# 01_MCU.net
KiCad netlist of a schematic drawn in Altium Designer
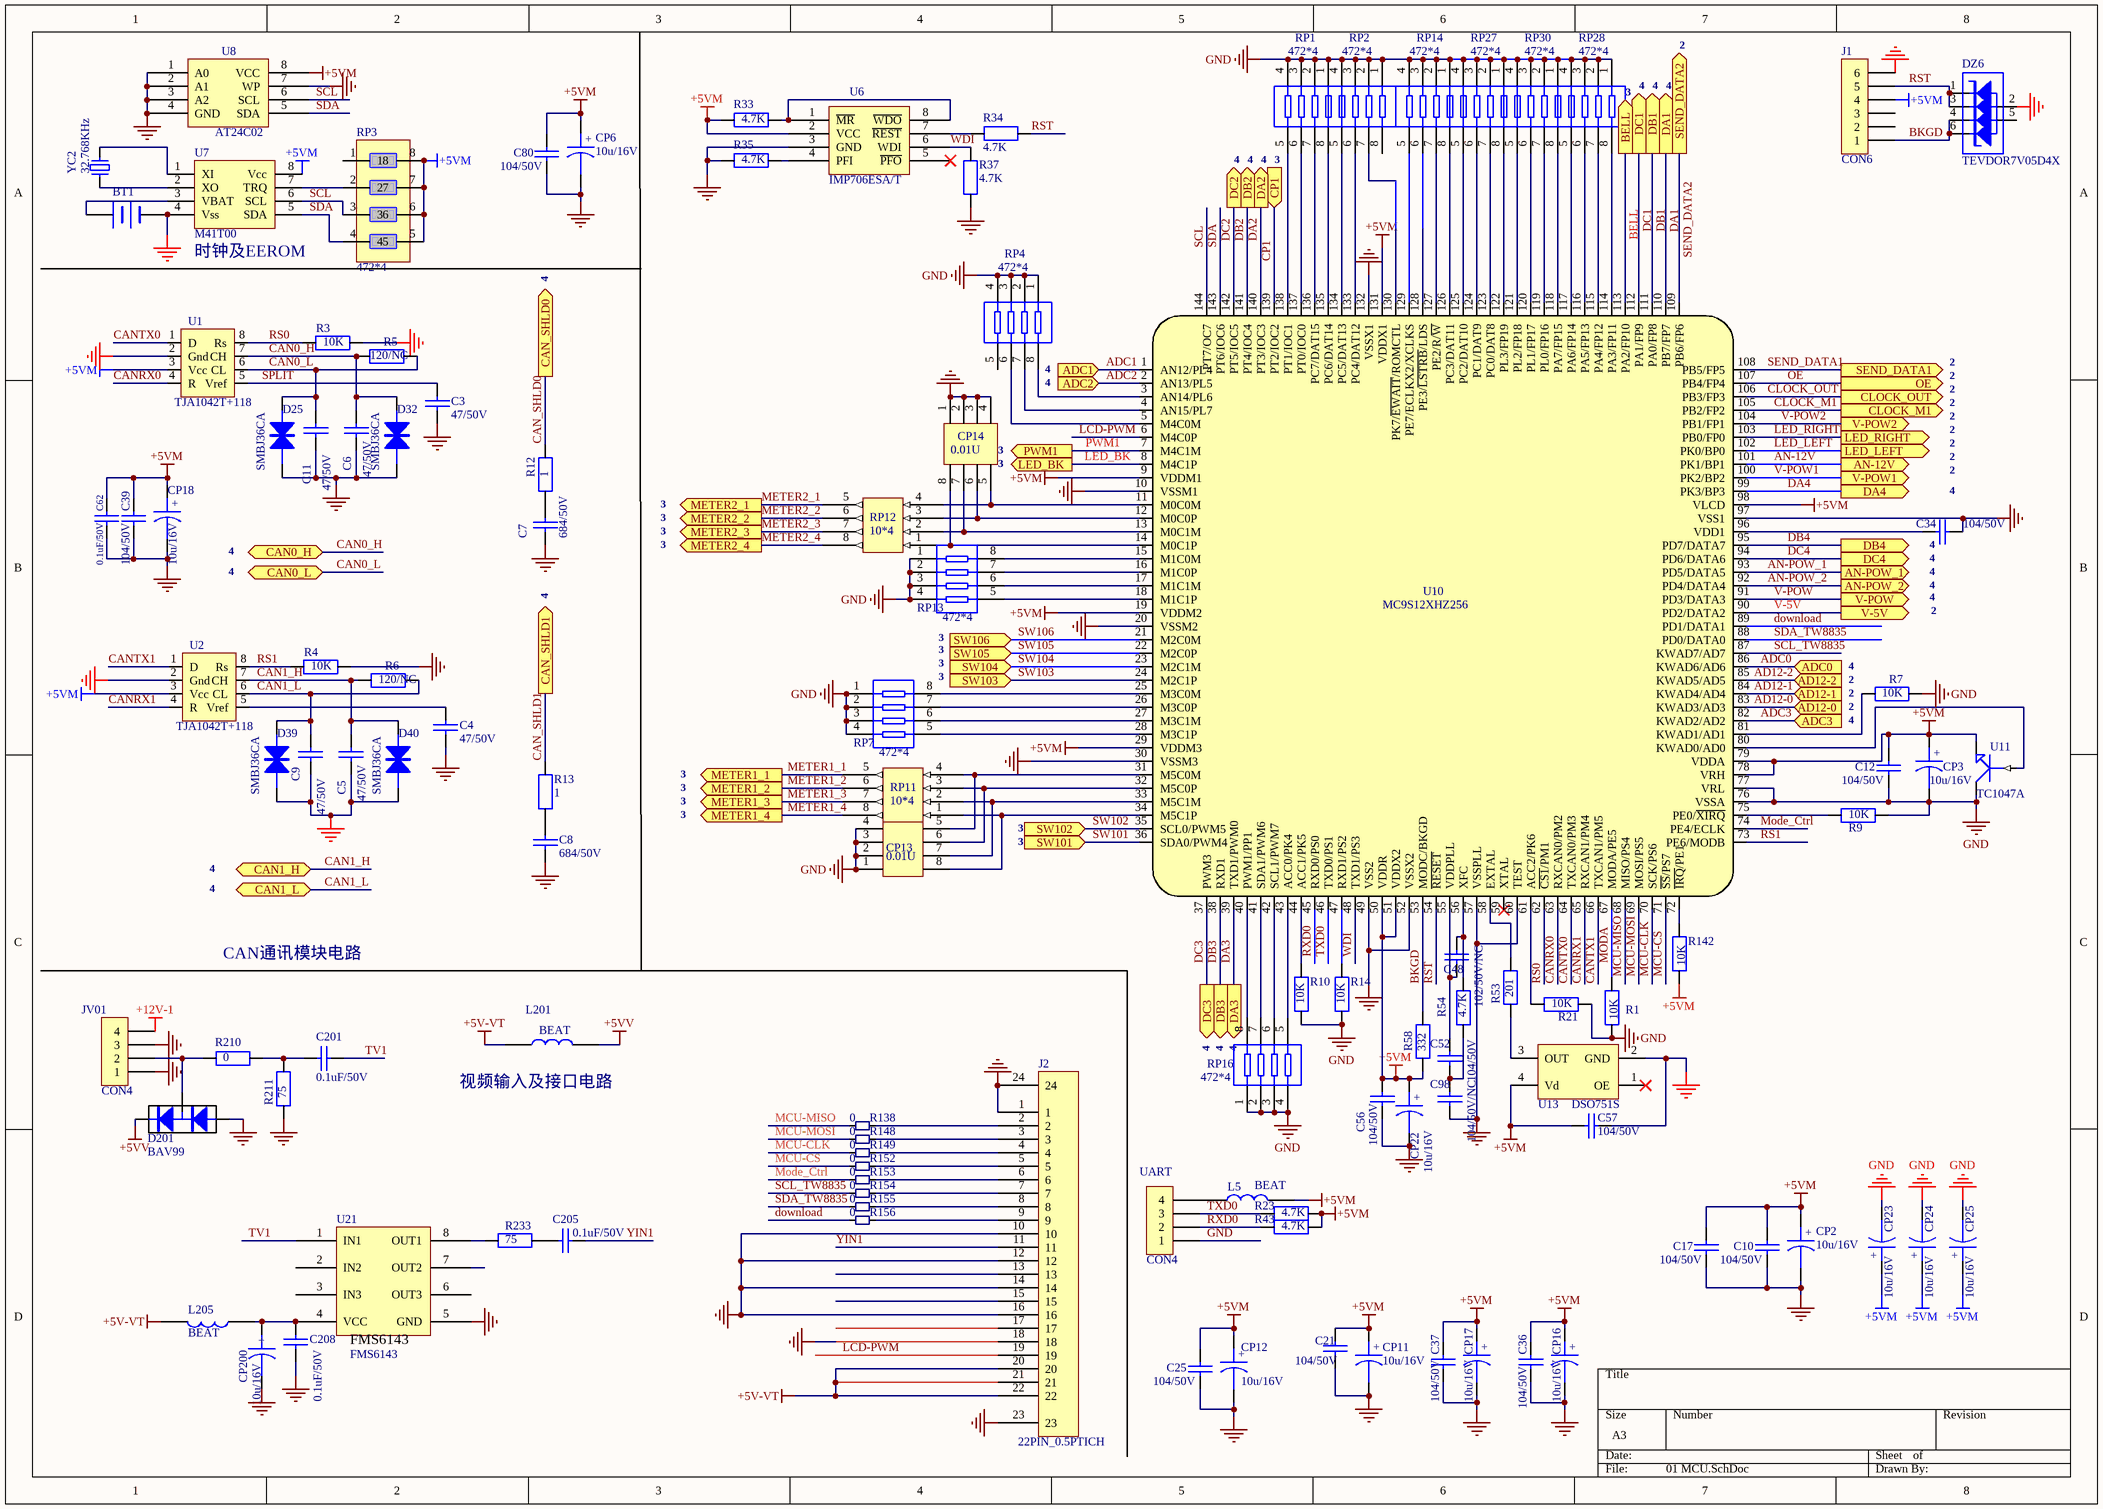
[diagram p0: 01 MCU.SchDoc]

(export (version "E")
  (design (tool "Eeschema 10.0.6"))
  (components
    (comp (ref "BT1")
      (value "~")
      (footprint "Battery 3")
      (description "Battery")
      (libsource (lib "*") (part "BATTERY"))
    )
    (comp (ref "C3")
      (value "47/50V")
      (footprint "CR0805")
      (description "Capacitor")
      (libsource (lib "*") (part "CAP"))
    )
    (comp (ref "C4")
      (value "47/50V")
      (footprint "CR0805")
      (description "Capacitor")
      (libsource (lib "*") (part "CAP"))
    )
    (comp (ref "C5")
      (value "47/50V")
      (footprint "CR0805")
      (description "Capacitor")
      (libsource (lib "*") (part "CAP"))
    )
    (comp (ref "C6")
      (value "47/50V")
      (footprint "CR0805")
      (description "Capacitor")
      (libsource (lib "*") (part "CAP"))
    )
    (comp (ref "C7")
      (value "684/50V")
      (footprint "CR1206")
      (description "Capacitor")
      (libsource (lib "*") (part "CAP"))
    )
    (comp (ref "C8")
      (value "684/50V")
      (footprint "CR1206")
      (description "Capacitor")
      (libsource (lib "*") (part "CAP"))
    )
    (comp (ref "C9")
      (value "47/50V")
      (footprint "CR0805")
      (description "Capacitor")
      (libsource (lib "*") (part "CAP"))
    )
    (comp (ref "C10")
      (value "104/50V")
      (footprint "CR0805")
      (description "Capacitor")
      (libsource (lib "*") (part "CAP"))
    )
    (comp (ref "C11")
      (value "47/50V")
      (footprint "CR0805")
      (description "Capacitor")
      (libsource (lib "*") (part "CAP"))
    )
    (comp (ref "C12")
      (value "104/50V")
      (footprint "CR0805")
      (description "Capacitor")
      (libsource (lib "*") (part "CAP"))
    )
    (comp (ref "C17")
      (value "104/50V")
      (footprint "CR0805")
      (description "Capacitor")
      (libsource (lib "*") (part "CAP"))
    )
    (comp (ref "C21")
      (value "104/50V")
      (footprint "CR0805")
      (description "Capacitor")
      (libsource (lib "*") (part "CAP"))
    )
    (comp (ref "C25")
      (value "104/50V")
      (footprint "CR0805")
      (description "Capacitor")
      (libsource (lib "*") (part "CAP"))
    )
    (comp (ref "C34")
      (value "104/50V")
      (footprint "CR0805")
      (description "Capacitor")
      (libsource (lib "*") (part "CAP"))
    )
    (comp (ref "C36")
      (value "104/50V")
      (footprint "CR0805")
      (description "Capacitor")
      (libsource (lib "*") (part "CAP"))
    )
    (comp (ref "C37")
      (value "104/50V")
      (footprint "CR0805")
      (description "Capacitor")
      (libsource (lib "*") (part "CAP"))
    )
    (comp (ref "C39")
      (value "104/50V")
      (footprint "CR0805")
      (description "Capacitor")
      (libsource (lib "*") (part "CAP"))
    )
    (comp (ref "C48")
      (value "102/50V/NC")
      (footprint "CR0805")
      (description "Capacitor")
      (libsource (lib "*") (part "CAP"))
    )
    (comp (ref "C52")
      (value "104/50V")
      (footprint "CR0805")
      (description "Capacitor")
      (libsource (lib "*") (part "CAP"))
    )
    (comp (ref "C56")
      (value "104/50V")
      (footprint "CR0805")
      (description "Capacitor")
      (libsource (lib "*") (part "CAP"))
    )
    (comp (ref "C57")
      (value "104/50V")
      (footprint "CR0805")
      (description "Capacitor")
      (libsource (lib "*") (part "CAP"))
    )
    (comp (ref "C62")
      (value "0.1uF/50V")
      (footprint "CR0805")
      (description "Capacitor")
      (libsource (lib "*") (part "CAP"))
    )
    (comp (ref "C80")
      (value "104/50V")
      (footprint "CR0805")
      (description "Capacitor")
      (libsource (lib "*") (part "CAP"))
    )
    (comp (ref "C98")
      (value "104/50V/NC")
      (footprint "CR0805")
      (description "Capacitor")
      (libsource (lib "*") (part "CAP"))
    )
    (comp (ref "C201")
      (value "0.1uF/50V")
      (footprint "CR0805")
      (description "贴片电容")
      (libsource (lib "YDM-SQ-1SCH") (part "CAP"))
    )
    (comp (ref "C205")
      (value "0.1uF/50V")
      (footprint "CR0805")
      (description "贴片电容")
      (libsource (lib "YDM-SQ-1SCH") (part "CAP"))
    )
    (comp (ref "C208")
      (value "0.1uF/50V")
      (footprint "CR0805")
      (description "Capacitor")
      (libsource (lib "*") (part "CAP"))
    )
    (comp (ref "CP2")
      (value "10u/16V")
      (footprint "CE1206")
      (description "Capacitor")
      (libsource (lib "*") (part "CAPACITOR POL"))
    )
    (comp (ref "CP3")
      (value "10u/16V")
      (footprint "CE1206")
      (description "Capacitor")
      (libsource (lib "*") (part "CAPACITOR POL"))
    )
    (comp (ref "CP6")
      (value "10u/16V")
      (footprint "CE1206")
      (description "Capacitor")
      (libsource (lib "*") (part "CAPACITOR POL"))
    )
    (comp (ref "CP11")
      (value "10u/16V")
      (footprint "CE1206")
      (description "Capacitor")
      (libsource (lib "*") (part "CAPACITOR POL"))
    )
    (comp (ref "CP12")
      (value "10u/16V")
      (footprint "CE1206")
      (description "Capacitor")
      (libsource (lib "*") (part "CAPACITOR POL"))
    )
    (comp (ref "CP13") (value "0.01U") (footprint "C4") (libsource (lib "*") (part "RC_ARRAY")))
    (comp (ref "CP14") (value "0.01U") (footprint "C4") (libsource (lib "") (part "RC_ARRAY_1")))
    (comp (ref "CP16")
      (value "10u/16V")
      (footprint "CE1206")
      (description "Capacitor")
      (libsource (lib "*") (part "CAPACITOR POL"))
    )
    (comp (ref "CP17")
      (value "10u/16V")
      (footprint "CE1206")
      (description "Capacitor")
      (libsource (lib "*") (part "CAPACITOR POL"))
    )
    (comp (ref "CP18")
      (value "10u/16V")
      (footprint "CE1206")
      (description "Capacitor")
      (libsource (lib "*") (part "CAPACITOR POL"))
    )
    (comp (ref "CP22")
      (value "10u/16V")
      (footprint "CE1206")
      (description "Capacitor")
      (libsource (lib "*") (part "CAPACITOR POL"))
    )
    (comp (ref "CP23")
      (value "10u/16V")
      (footprint "CE1206")
      (description "Capacitor")
      (libsource (lib "*") (part "CAPACITOR POL"))
    )
    (comp (ref "CP24")
      (value "10u/16V")
      (footprint "CE1206")
      (description "Capacitor")
      (libsource (lib "*") (part "CAPACITOR POL"))
    )
    (comp (ref "CP25")
      (value "10u/16V")
      (footprint "CE1206")
      (description "Capacitor")
      (libsource (lib "*") (part "CAPACITOR POL"))
    )
    (comp (ref "CP200")
      (value "10u/16V")
      (footprint "CE1206")
      (description "Capacitor")
      (libsource (lib "") (part "CAPACITOR POL_1"))
    )
    (comp (ref "D25") (value "SMBJ36CA") (footprint "SMB-D") (libsource (lib "YDM-SQ-1SCH") (part "TVS")))
    (comp (ref "D32") (value "SMBJ36CA") (footprint "SMB-D") (libsource (lib "YDM-SQ-1SCH") (part "TVS")))
    (comp (ref "D39") (value "SMBJ36CA") (footprint "SMB-D") (libsource (lib "YDM-SQ-1SCH") (part "TVS")))
    (comp (ref "D40") (value "SMBJ36CA") (footprint "SMB-D") (libsource (lib "YDM-SQ-1SCH") (part "TVS")))
    (comp (ref "D201")
      (value "BAV99")
      (footprint "SOT23")
      (description "双二极管")
      (libsource (lib "YDM-SQ-1SCH") (part "BAV23S"))
    )
    (comp (ref "DZ6")
      (value "TEVDOR7V05D4X")
      (footprint "SOT-457")
      (description "二极管排")
      (libsource (lib "yibiaoschlib") (part "TEVDOR7V05D4X"))
    )
    (comp (ref "J1")
      (value "CON6")
      (footprint "DIP 2X3 2.54mm")
      (description "Connector")
      (libsource (lib "*") (part "CON6"))
    )
    (comp (ref "J2")
      (value "22PIN_0.5PTICH")
      (footprint "FPC-22P")
      (libsource (lib "yibiaoschlib") (part "22PIN_0.5PTICH"))
    )
    (comp (ref "JV01")
      (value "CON4")
      (footprint "DIP 1X4 2.5mm")
      (description "Connector")
      (libsource (lib "YDM-SQ-1SCH") (part "CON4"))
    )
    (comp (ref "L5") (value "BEAT") (footprint "CR0805") (libsource (lib "") (part "BEAT_1")))
    (comp (ref "L201") (value "BEAT") (footprint "CR0805") (libsource (lib "") (part "BEAT_1")))
    (comp (ref "L205") (value "BEAT") (footprint "CR0805") (libsource (lib "YDM-SQ-1SCH") (part "BEAT")))
    (comp (ref "R1")
      (value "10K")
      (footprint "cr0805")
      (description "贴片电阻")
      (libsource (lib "*") (part "RES"))
    )
    (comp (ref "R3")
      (value "10K")
      (footprint "CR0805")
      (description "贴片电阻")
      (libsource (lib "*") (part "RES"))
    )
    (comp (ref "R4")
      (value "10K")
      (footprint "CR0805")
      (description "贴片电阻")
      (libsource (lib "*") (part "RES"))
    )
    (comp (ref "R5")
      (value "120/NC")
      (footprint "CR0805")
      (description "贴片电阻")
      (libsource (lib "*") (part "RES"))
    )
    (comp (ref "R6")
      (value "120/NC")
      (footprint "CR0805")
      (description "贴片电阻")
      (libsource (lib "*") (part "RES"))
    )
    (comp (ref "R7")
      (value "10K")
      (footprint "cr0805")
      (description "贴片电阻")
      (libsource (lib "*") (part "RES"))
    )
    (comp (ref "R9")
      (value "10K")
      (footprint "CR0805")
      (description "贴片电阻")
      (libsource (lib "*") (part "RES"))
    )
    (comp (ref "R10")
      (value "10K")
      (footprint "cr0805")
      (description "贴片电阻")
      (libsource (lib "*") (part "RES"))
    )
    (comp (ref "R12")
      (value "1")
      (footprint "CR0805")
      (description "贴片电阻")
      (libsource (lib "*") (part "RES"))
    )
    (comp (ref "R13")
      (value "1")
      (footprint "CR0805")
      (description "贴片电阻")
      (libsource (lib "*") (part "RES"))
    )
    (comp (ref "R14")
      (value "10K")
      (footprint "cr0805")
      (description "贴片电阻")
      (libsource (lib "*") (part "RES"))
    )
    (comp (ref "R21")
      (value "10K")
      (footprint "cr0805")
      (description "贴片电阻")
      (libsource (lib "*") (part "RES"))
    )
    (comp (ref "R23")
      (value "4.7K")
      (footprint "CR0805")
      (description "贴片电阻")
      (libsource (lib "*") (part "RES"))
    )
    (comp (ref "R33")
      (value "4.7K")
      (footprint "CR0805")
      (description "贴片电阻")
      (libsource (lib "YDM-SQ-1SCH") (part "RES"))
    )
    (comp (ref "R34")
      (value "4.7K")
      (footprint "CR0805")
      (description "贴片电阻")
      (libsource (lib "*") (part "RES"))
    )
    (comp (ref "R35")
      (value "4.7K")
      (footprint "CR0805")
      (description "贴片电阻")
      (libsource (lib "YDM-SQ-1SCH") (part "RES"))
    )
    (comp (ref "R37")
      (value "4.7K")
      (footprint "CR0805")
      (description "贴片电阻")
      (libsource (lib "*") (part "RES"))
    )
    (comp (ref "R43")
      (value "4.7K")
      (footprint "CR0805")
      (description "贴片电阻")
      (libsource (lib "*") (part "RES"))
    )
    (comp (ref "R53")
      (value "201")
      (footprint "CR0805")
      (description "贴片电阻")
      (libsource (lib "*") (part "RES"))
    )
    (comp (ref "R54")
      (value "4.7K")
      (footprint "CR0805")
      (description "贴片电阻")
      (libsource (lib "*") (part "RES"))
    )
    (comp (ref "R58")
      (value "332")
      (footprint "CR0805")
      (description "贴片电阻")
      (libsource (lib "*") (part "RES"))
    )
    (comp (ref "R138")
      (value "0")
      (footprint "CR0805")
      (description "贴片电阻")
      (libsource (lib "YDM-SQ-1SCH") (part "Resister mini"))
    )
    (comp (ref "R142")
      (value "10K")
      (footprint "cr0805")
      (description "贴片电阻")
      (libsource (lib "*") (part "RES"))
    )
    (comp (ref "R148")
      (value "0")
      (footprint "CR0805")
      (description "贴片电阻")
      (libsource (lib "YDM-SQ-1SCH") (part "Resister mini"))
    )
    (comp (ref "R149")
      (value "0")
      (footprint "CR0805")
      (description "贴片电阻")
      (libsource (lib "YDM-SQ-1SCH") (part "Resister mini"))
    )
    (comp (ref "R152")
      (value "0")
      (footprint "CR0805")
      (description "贴片电阻")
      (libsource (lib "YDM-SQ-1SCH") (part "Resister mini"))
    )
    (comp (ref "R153")
      (value "0")
      (footprint "CR0805")
      (description "贴片电阻")
      (libsource (lib "YDM-SQ-1SCH") (part "Resister mini"))
    )
    (comp (ref "R154")
      (value "0")
      (footprint "CR0805")
      (description "贴片电阻")
      (libsource (lib "YDM-SQ-1SCH") (part "Resister mini"))
    )
    (comp (ref "R155")
      (value "0")
      (footprint "CR0805")
      (description "贴片电阻")
      (libsource (lib "YDM-SQ-1SCH") (part "Resister mini"))
    )
    (comp (ref "R156")
      (value "0")
      (footprint "CR0805")
      (description "贴片电阻")
      (libsource (lib "YDM-SQ-1SCH") (part "Resister mini"))
    )
    (comp (ref "R210")
      (value "0")
      (footprint "CR0805")
      (description "贴片电阻")
      (libsource (lib "YDM-SQ-1SCH") (part "RES"))
    )
    (comp (ref "R211")
      (value "75")
      (footprint "CR0805")
      (description "贴片电阻")
      (libsource (lib "YDM-SQ-1SCH") (part "RES"))
    )
    (comp (ref "R233")
      (value "75")
      (footprint "CR0805")
      (description "贴片电阻")
      (libsource (lib "YDM-SQ-1SCH") (part "RES"))
    )
    (comp (ref "RP1")
      (value "472*4")
      (footprint "R4")
      (description "贴片排阻")
      (libsource (lib "*") (part "R_LINE4"))
    )
    (comp (ref "RP2")
      (value "472*4")
      (footprint "R4")
      (description "贴片排阻")
      (libsource (lib "*") (part "R_LINE4"))
    )
    (comp (ref "RP3") (value "472*4") (footprint "R4") (libsource (lib "*") (part "R_ARRAY")))
    (comp (ref "RP4")
      (value "472*4")
      (footprint "R4")
      (description "贴片排阻")
      (libsource (lib "*") (part "R_LINE4"))
    )
    (comp (ref "RP7")
      (value "472*4")
      (footprint "R4")
      (description "贴片排阻")
      (libsource (lib "*") (part "R_LINE4"))
    )
    (comp (ref "RP11") (value "10*4") (footprint "R4") (libsource (lib "*") (part "R_PAI")))
    (comp (ref "RP12") (value "10*4") (footprint "R4") (libsource (lib "*") (part "R_PAI")))
    (comp (ref "RP13")
      (value "472*4")
      (footprint "R4")
      (description "贴片排阻")
      (libsource (lib "*") (part "R_LINE4"))
    )
    (comp (ref "RP14")
      (value "472*4")
      (footprint "R4")
      (description "贴片排阻")
      (libsource (lib "*") (part "R_LINE4"))
    )
    (comp (ref "RP16")
      (value "472*4")
      (footprint "R4")
      (description "贴片排阻")
      (libsource (lib "*") (part "R_LINE4"))
    )
    (comp (ref "RP27")
      (value "472*4")
      (footprint "R4")
      (description "贴片排阻")
      (libsource (lib "*") (part "R_LINE4"))
    )
    (comp (ref "RP28")
      (value "472*4")
      (footprint "R4")
      (description "贴片排阻")
      (libsource (lib "*") (part "R_LINE4"))
    )
    (comp (ref "RP30")
      (value "472*4")
      (footprint "R4")
      (description "贴片排阻")
      (libsource (lib "*") (part "R_LINE4"))
    )
    (comp (ref "U1") (value "TJA1042T+118") (footprint "SO-8") (libsource (lib "*") (part "SN65HVD251")))
    (comp (ref "U2") (value "TJA1042T+118") (footprint "SO-8") (libsource (lib "*") (part "SN65HVD251")))
    (comp (ref "U6") (value "IMP706ESA/T") (footprint "SO-8") (libsource (lib "YDM-SQ-1SCH") (part "IMP706")))
    (comp (ref "U7")
      (value "M41T00")
      (footprint "SO-8")
      (description "IC")
      (libsource (lib "*") (part "M41T00"))
    )
    (comp (ref "U8")
      (value "AT24C02")
      (footprint "SO-8")
      (description "IC")
      (libsource (lib "*") (part "AT24C02"))
    )
    (comp (ref "U10")
      (value "MC9S12XHZ256")
      (footprint "LQFP-144")
      (libsource (lib "YDM-SQ-1SCH") (part "MC9S12XHZ256"))
    )
    (comp (ref "U11") (value "TC1047A") (footprint "SOT23") (libsource (lib "YDM-SQ-1SCH") (part "DTC143")))
    (comp (ref "U13") (value "DSO751S") (footprint "SMD-CYC") (libsource (lib "*") (part "POW_CRY")))
    (comp (ref "U21")
      (value "FMS6143")
      (footprint "SO-8")
      (description "IC-视频滤波")
      (libsource (lib "HNS-SCH") (part "FMS6143"))
    )
    (comp (ref "UART")
      (value "CON4")
      (footprint "DIP 1X4 2.5mm")
      (description "Connector")
      (libsource (lib "YDM-SQ-1SCH") (part "CON4"))
    )
    (comp (ref "YC2")
      (value "32.768KHz")
      (footprint "SM CYC NX3215SA")
      (libsource (lib "*") (part "CRYSTAL0"))
    )
  )
  (nets
    (net (code "1") (name "+5V-VT") (class "Default")
      (node (ref "J2") (pin "20") (pinfunction "20_20") (pintype "passive"))
      (node (ref "J2") (pin "21") (pinfunction "21_21") (pintype "passive"))
      (node (ref "J2") (pin "22") (pinfunction "22_22") (pintype "passive"))
      (node (ref "L201") (pin "1") (pinfunction "1_1") (pintype "passive"))
      (node (ref "L205") (pin "1") (pinfunction "1_1") (pintype "passive"))
    )
    (net (code "2") (name "+5VM") (class "Default")
      (node (ref "C10") (pin "1") (pinfunction "1_1") (pintype "passive"))
      (node (ref "C12") (pin "1") (pinfunction "1_1") (pintype "passive"))
      (node (ref "C17") (pin "1") (pinfunction "1_1") (pintype "passive"))
      (node (ref "C21") (pin "2") (pinfunction "2_2") (pintype "passive"))
      (node (ref "C25") (pin "1") (pinfunction "1_1") (pintype "passive"))
      (node (ref "C36") (pin "1") (pinfunction "1_1") (pintype "passive"))
      (node (ref "C37") (pin "1") (pinfunction "1_1") (pintype "passive"))
      (node (ref "C39") (pin "2") (pinfunction "2_2") (pintype "passive"))
      (node (ref "C56") (pin "1") (pinfunction "1_1") (pintype "passive"))
      (node (ref "C57") (pin "1") (pinfunction "1_1") (pintype "passive"))
      (node (ref "C62") (pin "1") (pinfunction "1_1") (pintype "passive"))
      (node (ref "C80") (pin "1") (pinfunction "1_1") (pintype "passive"))
      (node (ref "CP11") (pin "1") (pinfunction "1_1") (pintype "passive"))
      (node (ref "CP12") (pin "1") (pinfunction "1_1") (pintype "passive"))
      (node (ref "CP16") (pin "1") (pinfunction "1_1") (pintype "passive"))
      (node (ref "CP17") (pin "1") (pinfunction "1_1") (pintype "passive"))
      (node (ref "CP18") (pin "1") (pinfunction "1_1") (pintype "passive"))
      (node (ref "CP2") (pin "1") (pinfunction "1_1") (pintype "passive"))
      (node (ref "CP22") (pin "1") (pinfunction "1_1") (pintype "passive"))
      (node (ref "CP23") (pin "1") (pinfunction "1_1") (pintype "passive"))
      (node (ref "CP24") (pin "1") (pinfunction "1_1") (pintype "passive"))
      (node (ref "CP25") (pin "1") (pinfunction "1_1") (pintype "passive"))
      (node (ref "CP3") (pin "1") (pinfunction "1_1") (pintype "passive"))
      (node (ref "CP6") (pin "1") (pinfunction "1_1") (pintype "passive"))
      (node (ref "J1") (pin "4") (pinfunction "4_4") (pintype "passive"))
      (node (ref "L5") (pin "2") (pinfunction "2_2") (pintype "passive"))
      (node (ref "R142") (pin "2") (pinfunction "2_2") (pintype "passive"))
      (node (ref "R23") (pin "2") (pinfunction "2_2") (pintype "passive"))
      (node (ref "R33") (pin "2") (pinfunction "2_2") (pintype "passive"))
      (node (ref "R43") (pin "2") (pinfunction "2_2") (pintype "passive"))
      (node (ref "R58") (pin "1") (pinfunction "1_1") (pintype "passive"))
      (node (ref "RP3") (pin "5") (pinfunction "5_5") (pintype "passive"))
      (node (ref "RP3") (pin "6") (pinfunction "6_6") (pintype "passive"))
      (node (ref "RP3") (pin "7") (pinfunction "7_7") (pintype "passive"))
      (node (ref "RP3") (pin "8") (pinfunction "8_8") (pintype "passive"))
      (node (ref "U1") (pin "3") (pinfunction "Vcc_3") (pintype "passive"))
      (node (ref "U10") (pin "131") (pinfunction "VDDX1_131") (pintype "passive"))
      (node (ref "U10") (pin "19") (pinfunction "VDDM2_19") (pintype "passive"))
      (node (ref "U10") (pin "29") (pinfunction "VDDM3_29") (pintype "passive"))
      (node (ref "U10") (pin "50") (pinfunction "VDDR_50") (pintype "passive"))
      (node (ref "U10") (pin "51") (pinfunction "VDDX2_51") (pintype "passive"))
      (node (ref "U10") (pin "78") (pinfunction "VRH_78") (pintype "passive"))
      (node (ref "U10") (pin "79") (pinfunction "VDDA_79") (pintype "passive"))
      (node (ref "U10") (pin "9") (pinfunction "VDDM1_9") (pintype "passive"))
      (node (ref "U10") (pin "98") (pinfunction "VLCD_98") (pintype "passive"))
      (node (ref "U11") (pin "1") (pinfunction "E_1") (pintype "passive"))
      (node (ref "U13") (pin "4") (pinfunction "Vd_4") (pintype "passive"))
      (node (ref "U2") (pin "3") (pinfunction "Vcc_3") (pintype "passive"))
      (node (ref "U6") (pin "2") (pinfunction "VCC_2") (pintype "passive"))
      (node (ref "U7") (pin "8") (pinfunction "Vcc_8") (pintype "passive"))
      (node (ref "U8") (pin "8") (pinfunction "VCC_8") (pintype "passive"))
    )
    (net (code "3") (name "+5VV") (class "Default")
      (node (ref "D201") (pin "2") (pintype "passive"))
      (node (ref "L201") (pin "2") (pinfunction "2_2") (pintype "passive"))
    )
    (net (code "4") (name "+12V-1") (class "Default")
      (node (ref "JV01") (pin "4") (pinfunction "4_4") (pintype "passive"))
    )
    (net (code "6") (name "/AD12-0") (class "Default")
      (node (ref "U10") (pin "83") (pinfunction "KWAD3/AD3_83") (pintype "passive"))
    )
    (net (code "7") (name "/AD12-1") (class "Default")
      (node (ref "U10") (pin "84") (pinfunction "KWAD4/AD4_84") (pintype "passive"))
    )
    (net (code "8") (name "/AD12-2") (class "Default")
      (node (ref "U10") (pin "85") (pinfunction "KWAD5/AD5_85") (pintype "passive"))
    )
    (net (code "9") (name "/ADC0") (class "Default")
      (node (ref "U10") (pin "86") (pinfunction "KWAD6/AD6_86") (pintype "passive"))
    )
    (net (code "10") (name "/ADC1") (class "Default")
      (node (ref "U10") (pin "1") (pinfunction "AN12/PL4_1") (pintype "passive"))
    )
    (net (code "11") (name "/ADC2") (class "Default")
      (node (ref "U10") (pin "2") (pinfunction "AN13/PL5_2") (pintype "passive"))
    )
    (net (code "12") (name "/ADC3") (class "Default")
      (node (ref "U10") (pin "82") (pinfunction "KWAD2/AD2_82") (pintype "passive"))
    )
    (net (code "13") (name "/AN-12V") (class "Default")
      (node (ref "U10") (pin "101") (pinfunction "PK1/BP1_101") (pintype "passive"))
    )
    (net (code "14") (name "/AN-POW_1") (class "Default")
      (node (ref "U10") (pin "93") (pinfunction "PD5/DATA5_93") (pintype "passive"))
    )
    (net (code "15") (name "/AN-POW_2") (class "Default")
      (node (ref "U10") (pin "92") (pinfunction "PD4/DATA4_92") (pintype "passive"))
    )
    (net (code "16") (name "/BELL") (class "Default")
      (node (ref "U10") (pin "113") (pinfunction "PA2/FP10_113") (pintype "passive"))
    )
    (net (code "17") (name "/BKGD") (class "Default")
      (node (ref "DZ6") (pin "4") (pintype "passive"))
      (node (ref "DZ6") (pin "6") (pintype "passive"))
      (node (ref "J1") (pin "1") (pinfunction "1_1") (pintype "passive"))
      (node (ref "R58") (pin "2") (pinfunction "2_2") (pintype "passive"))
      (node (ref "U10") (pin "53") (pinfunction "MODC/BKGD_53") (pintype "passive"))
    )
    (net (code "18") (name "/CAN0_H") (class "Default")
      (node (ref "C6") (pin "2") (pinfunction "2_2") (pintype "passive"))
      (node (ref "D32") (pin "2") (pinfunction "2_2") (pintype "passive"))
      (node (ref "R5") (pin "2") (pinfunction "2_2") (pintype "passive"))
      (node (ref "U1") (pin "7") (pinfunction "CH_7") (pintype "passive"))
    )
    (net (code "19") (name "/CAN0_L") (class "Default")
      (node (ref "C11") (pin "2") (pinfunction "2_2") (pintype "passive"))
      (node (ref "D25") (pin "2") (pinfunction "2_2") (pintype "passive"))
      (node (ref "R5") (pin "1") (pinfunction "1_1") (pintype "passive"))
      (node (ref "U1") (pin "6") (pinfunction "CL_6") (pintype "passive"))
    )
    (net (code "20") (name "/CAN1_H") (class "Default")
      (node (ref "C5") (pin "2") (pinfunction "2_2") (pintype "passive"))
      (node (ref "D40") (pin "2") (pinfunction "2_2") (pintype "passive"))
      (node (ref "R6") (pin "2") (pinfunction "2_2") (pintype "passive"))
      (node (ref "U2") (pin "7") (pinfunction "CH_7") (pintype "passive"))
    )
    (net (code "21") (name "/CAN1_L") (class "Default")
      (node (ref "C9") (pin "2") (pinfunction "2_2") (pintype "passive"))
      (node (ref "D39") (pin "2") (pinfunction "2_2") (pintype "passive"))
      (node (ref "R6") (pin "1") (pinfunction "1_1") (pintype "passive"))
      (node (ref "U2") (pin "6") (pinfunction "CL_6") (pintype "passive"))
    )
    (net (code "22") (name "/CANRX0") (class "Default")
      (node (ref "U1") (pin "4") (pinfunction "R_4") (pintype "passive"))
      (node (ref "U10") (pin "63") (pinfunction "RXCAN0/PM2_63") (pintype "passive"))
    )
    (net (code "23") (name "/CANRX1") (class "Default")
      (node (ref "U10") (pin "65") (pinfunction "RXCAN1/PM4_65") (pintype "passive"))
      (node (ref "U2") (pin "4") (pinfunction "R_4") (pintype "passive"))
    )
    (net (code "24") (name "/CANTX0") (class "Default")
      (node (ref "U1") (pin "1") (pinfunction "D_1") (pintype "passive"))
      (node (ref "U10") (pin "64") (pinfunction "TXCAN0/PM3_64") (pintype "passive"))
    )
    (net (code "25") (name "/CANTX1") (class "Default")
      (node (ref "U10") (pin "66") (pinfunction "TXCAN1/PM5_66") (pintype "passive"))
      (node (ref "U2") (pin "1") (pinfunction "D_1") (pintype "passive"))
    )
    (net (code "26") (name "/CAN_SHLD0") (class "Default")
      (node (ref "R12") (pin "2") (pinfunction "2_2") (pintype "passive"))
    )
    (net (code "27") (name "/CAN_SHLD1") (class "Default")
      (node (ref "R13") (pin "2") (pinfunction "2_2") (pintype "passive"))
    )
    (net (code "28") (name "/CLOCK_M1") (class "Default")
      (node (ref "U10") (pin "105") (pinfunction "PB2/FP2_105") (pintype "passive"))
    )
    (net (code "29") (name "/CLOCK_OUT") (class "Default")
      (node (ref "U10") (pin "106") (pinfunction "PB3/FP3_106") (pintype "passive"))
    )
    (net (code "30") (name "/CP1") (class "Default")
      (node (ref "U10") (pin "139") (pinfunction "PT2/IOC2_139") (pintype "passive"))
    )
    (net (code "31") (name "/DA1") (class "Default")
      (node (ref "U10") (pin "110") (pinfunction "PB7/FP7_110") (pintype "passive"))
    )
    (net (code "32") (name "/DA2") (class "Default")
      (node (ref "U10") (pin "140") (pinfunction "PT3/IOC3_140") (pintype "passive"))
    )
    (net (code "33") (name "/DA3") (class "Default")
      (node (ref "U10") (pin "39") (pinfunction "TXD1/PWM0_39") (pintype "passive"))
    )
    (net (code "34") (name "/DA4") (class "Default")
      (node (ref "U10") (pin "99") (pinfunction "PK3/BP3_99") (pintype "passive"))
    )
    (net (code "35") (name "/DB1") (class "Default")
      (node (ref "U10") (pin "111") (pinfunction "PA0/FP8_111") (pintype "passive"))
    )
    (net (code "36") (name "/DB2") (class "Default")
      (node (ref "U10") (pin "141") (pinfunction "PT4/IOC4_141") (pintype "passive"))
    )
    (net (code "37") (name "/DB3") (class "Default")
      (node (ref "U10") (pin "38") (pinfunction "RXD1_38") (pintype "passive"))
    )
    (net (code "38") (name "/DB4") (class "Default")
      (node (ref "U10") (pin "95") (pinfunction "PD7/DATA7_95") (pintype "passive"))
    )
    (net (code "39") (name "/DC1") (class "Default")
      (node (ref "U10") (pin "112") (pinfunction "PA1/FP9_112") (pintype "passive"))
    )
    (net (code "40") (name "/DC2") (class "Default")
      (node (ref "U10") (pin "142") (pinfunction "PT5/IOC5_142") (pintype "passive"))
    )
    (net (code "41") (name "/DC3") (class "Default")
      (node (ref "U10") (pin "37") (pinfunction "PWM3_37") (pintype "passive"))
    )
    (net (code "42") (name "/DC4") (class "Default")
      (node (ref "U10") (pin "94") (pinfunction "PD6/DATA6_94") (pintype "passive"))
    )
    (net (code "43") (name "/LCD-PWM") (class "Default")
      (node (ref "J2") (pin "19") (pinfunction "19_19") (pintype "passive"))
      (node (ref "U10") (pin "6") (pinfunction "M4C0P_6") (pintype "passive"))
    )
    (net (code "44") (name "/LED_BK") (class "Default")
      (node (ref "U10") (pin "8") (pinfunction "M4C1P_8") (pintype "passive"))
    )
    (net (code "45") (name "/LED_LEFT") (class "Default")
      (node (ref "U10") (pin "102") (pinfunction "PK0/BP0_102") (pintype "passive"))
    )
    (net (code "46") (name "/LED_RIGHT") (class "Default")
      (node (ref "U10") (pin "103") (pinfunction "PB0/FP0_103") (pintype "passive"))
    )
    (net (code "47") (name "/MCU-CLK") (class "Default")
      (node (ref "R149") (pin "2") (pinfunction "2_2") (pintype "passive"))
      (node (ref "U10") (pin "70") (pinfunction "SCK/PS6_70") (pintype "passive"))
    )
    (net (code "48") (name "/MCU-CS") (class "Default")
      (node (ref "R152") (pin "2") (pinfunction "2_2") (pintype "passive"))
      (node (ref "U10") (pin "71") (pinfunction "~{SS}/PS7_71") (pintype "passive"))
    )
    (net (code "49") (name "/MCU-MISO") (class "Default")
      (node (ref "R138") (pin "2") (pinfunction "2_2") (pintype "passive"))
      (node (ref "U10") (pin "68") (pinfunction "MISO/PS4_68") (pintype "passive"))
    )
    (net (code "50") (name "/MCU-MOSI") (class "Default")
      (node (ref "R148") (pin "2") (pinfunction "2_2") (pintype "passive"))
      (node (ref "U10") (pin "69") (pinfunction "MOSI/PS5_69") (pintype "passive"))
    )
    (net (code "51") (name "/METER1_1") (class "Default")
      (node (ref "RP11") (pin "5") (pinfunction "5_5") (pintype "output"))
    )
    (net (code "52") (name "/METER1_2") (class "Default")
      (node (ref "RP11") (pin "6") (pinfunction "6_6") (pintype "output"))
    )
    (net (code "53") (name "/METER1_3") (class "Default")
      (node (ref "RP11") (pin "7") (pinfunction "7_7") (pintype "output"))
    )
    (net (code "54") (name "/METER1_4") (class "Default")
      (node (ref "RP11") (pin "8") (pinfunction "8_8") (pintype "output"))
    )
    (net (code "55") (name "/METER2_1") (class "Default")
      (node (ref "RP12") (pin "5") (pinfunction "5_5") (pintype "output"))
    )
    (net (code "56") (name "/METER2_2") (class "Default")
      (node (ref "RP12") (pin "6") (pinfunction "6_6") (pintype "output"))
    )
    (net (code "57") (name "/METER2_3") (class "Default")
      (node (ref "RP12") (pin "7") (pinfunction "7_7") (pintype "output"))
    )
    (net (code "58") (name "/METER2_4") (class "Default")
      (node (ref "RP12") (pin "8") (pinfunction "8_8") (pintype "output"))
    )
    (net (code "59") (name "/MODA") (class "Default")
      (node (ref "R1") (pin "1") (pinfunction "1_1") (pintype "passive"))
      (node (ref "U10") (pin "67") (pinfunction "MODA/PE5_67") (pintype "passive"))
    )
    (net (code "60") (name "/Mode_Ctrl") (class "Default")
      (node (ref "R153") (pin "2") (pinfunction "2_2") (pintype "passive"))
      (node (ref "U10") (pin "74") (pinfunction "PE4/ECLK_74") (pintype "passive"))
    )
    (net (code "61") (name "/OE") (class "Default")
      (node (ref "U10") (pin "107") (pinfunction "PB4/FP4_107") (pintype "passive"))
    )
    (net (code "62") (name "/PWM1") (class "Default")
      (node (ref "U10") (pin "7") (pinfunction "M4C1M_7") (pintype "passive"))
    )
    (net (code "63") (name "/RS0") (class "Default")
      (node (ref "R3") (pin "1") (pinfunction "1_1") (pintype "passive"))
      (node (ref "U1") (pin "8") (pinfunction "Rs_8") (pintype "passive"))
      (node (ref "U10") (pin "62") (pinfunction "~{CS1}/PM1_62") (pintype "passive"))
    )
    (net (code "64") (name "/RS1") (class "Default")
      (node (ref "R4") (pin "1") (pinfunction "1_1") (pintype "passive"))
      (node (ref "U10") (pin "73") (pinfunction "PE6/MODB_73") (pintype "passive"))
      (node (ref "U2") (pin "8") (pinfunction "Rs_8") (pintype "passive"))
    )
    (net (code "65") (name "/RST") (class "Default")
      (node (ref "DZ6") (pin "1") (pintype "passive"))
      (node (ref "DZ6") (pin "3") (pintype "passive"))
      (node (ref "J1") (pin "5") (pinfunction "5_5") (pintype "passive"))
      (node (ref "R34") (pin "2") (pinfunction "2_2") (pintype "passive"))
      (node (ref "U10") (pin "54") (pinfunction "~{RESET}_54") (pintype "passive"))
    )
    (net (code "66") (name "/RXD0") (class "Default")
      (node (ref "R43") (pin "1") (pinfunction "1_1") (pintype "passive"))
      (node (ref "U10") (pin "45") (pinfunction "RXD0/PS0_45") (pintype "passive"))
      (node (ref "UART") (pin "2") (pinfunction "2_2") (pintype "passive"))
    )
    (net (code "67") (name "/SCL") (class "Default")
      (node (ref "RP3") (pin "3") (pinfunction "3_3") (pintype "passive"))
      (node (ref "U10") (pin "144") (pinfunction "PT7/OC7_144") (pintype "passive"))
      (node (ref "U7") (pin "6") (pinfunction "SCL_6") (pintype "passive"))
      (node (ref "U8") (pin "6") (pinfunction "SCL_6") (pintype "passive"))
    )
    (net (code "68") (name "/SCL_TW8835") (class "Default")
      (node (ref "R154") (pin "2") (pinfunction "2_2") (pintype "passive"))
      (node (ref "U10") (pin "87") (pinfunction "KWAD7/AD7_87") (pintype "passive"))
    )
    (net (code "69") (name "/SDA") (class "Default")
      (node (ref "RP3") (pin "4") (pinfunction "4_4") (pintype "passive"))
      (node (ref "U10") (pin "143") (pinfunction "PT6/IOC6_143") (pintype "passive"))
      (node (ref "U7") (pin "5") (pinfunction "SDA_5") (pintype "passive"))
      (node (ref "U8") (pin "5") (pinfunction "SDA_5") (pintype "passive"))
    )
    (net (code "70") (name "/SDA_TW8835") (class "Default")
      (node (ref "R155") (pin "2") (pinfunction "2_2") (pintype "passive"))
      (node (ref "U10") (pin "88") (pinfunction "PD0/DATA0_88") (pintype "passive"))
    )
    (net (code "71") (name "/SEND_DATA1") (class "Default")
      (node (ref "U10") (pin "108") (pinfunction "PB5/FP5_108") (pintype "passive"))
    )
    (net (code "72") (name "/SEND_DATA2") (class "Default")
      (node (ref "U10") (pin "109") (pinfunction "PB6/FP6_109") (pintype "passive"))
    )
    (net (code "73") (name "/SPLIT") (class "Default")
      (node (ref "C3") (pin "1") (pinfunction "1_1") (pintype "passive"))
      (node (ref "U1") (pin "5") (pinfunction "Vref_5") (pintype "passive"))
    )
    (net (code "74") (name "/SW101") (class "Default")
      (node (ref "U10") (pin "36") (pinfunction "SDA0/PWM4_36") (pintype "passive"))
    )
    (net (code "75") (name "/SW102") (class "Default")
      (node (ref "U10") (pin "35") (pinfunction "SCL0/PWM5_35") (pintype "passive"))
    )
    (net (code "76") (name "/SW103") (class "Default")
      (node (ref "U10") (pin "24") (pinfunction "M2C1P_24") (pintype "passive"))
    )
    (net (code "77") (name "/SW104") (class "Default")
      (node (ref "U10") (pin "23") (pinfunction "M2C1M_23") (pintype "passive"))
    )
    (net (code "78") (name "/SW105") (class "Default")
      (node (ref "U10") (pin "22") (pinfunction "M2C0P_22") (pintype "passive"))
    )
    (net (code "79") (name "/SW106") (class "Default")
      (node (ref "U10") (pin "21") (pinfunction "M2C0M_21") (pintype "passive"))
    )
    (net (code "80") (name "/TV1") (class "Default")
      (node (ref "C201") (pin "2") (pinfunction "2_2") (pintype "passive"))
      (node (ref "U21") (pin "1") (pinfunction "IN1_1") (pintype "passive"))
    )
    (net (code "81") (name "/TXD0") (class "Default")
      (node (ref "R23") (pin "1") (pinfunction "1_1") (pintype "passive"))
      (node (ref "U10") (pin "46") (pinfunction "TXD0/PS1_46") (pintype "passive"))
      (node (ref "UART") (pin "3") (pinfunction "3_3") (pintype "passive"))
    )
    (net (code "82") (name "/V-5V") (class "Default")
      (node (ref "U10") (pin "90") (pinfunction "PD2/DATA2_90") (pintype "passive"))
    )
    (net (code "83") (name "/V-POW") (class "Default")
      (node (ref "U10") (pin "91") (pinfunction "PD3/DATA3_91") (pintype "passive"))
    )
    (net (code "84") (name "/V-POW1") (class "Default")
      (node (ref "U10") (pin "100") (pinfunction "PK2/BP2_100") (pintype "passive"))
    )
    (net (code "85") (name "/V-POW2") (class "Default")
      (node (ref "U10") (pin "104") (pinfunction "PB1/FP1_104") (pintype "passive"))
    )
    (net (code "86") (name "/WDI") (class "Default")
      (node (ref "R37") (pin "1") (pinfunction "1_1") (pintype "passive"))
      (node (ref "U10") (pin "48") (pinfunction "TXD1/PS3_48") (pintype "passive"))
      (node (ref "U6") (pin "6") (pinfunction "WDI_6") (pintype "passive"))
    )
    (net (code "87") (name "/YIN1") (class "Default")
      (node (ref "C205") (pin "2") (pinfunction "2_2") (pintype "passive"))
      (node (ref "J2") (pin "11") (pinfunction "11_11") (pintype "passive"))
    )
    (net (code "88") (name "/download") (class "Default")
      (node (ref "R156") (pin "2") (pinfunction "2_2") (pintype "passive"))
      (node (ref "U10") (pin "89") (pinfunction "PD1/DATA1_89") (pintype "passive"))
    )
    (net (code "89") (name "GND") (class "Default")
      (node (ref "BT1") (pin "2") (pinfunction "-_2") (pintype "passive"))
      (node (ref "C10") (pin "2") (pinfunction "2_2") (pintype "passive"))
      (node (ref "C11") (pin "1") (pinfunction "1_1") (pintype "passive"))
      (node (ref "C12") (pin "2") (pinfunction "2_2") (pintype "passive"))
      (node (ref "C17") (pin "2") (pinfunction "2_2") (pintype "passive"))
      (node (ref "C208") (pin "2") (pinfunction "2_2") (pintype "passive"))
      (node (ref "C21") (pin "1") (pinfunction "1_1") (pintype "passive"))
      (node (ref "C25") (pin "2") (pinfunction "2_2") (pintype "passive"))
      (node (ref "C3") (pin "2") (pinfunction "2_2") (pintype "passive"))
      (node (ref "C34") (pin "2") (pinfunction "2_2") (pintype "passive"))
      (node (ref "C36") (pin "2") (pinfunction "2_2") (pintype "passive"))
      (node (ref "C37") (pin "2") (pinfunction "2_2") (pintype "passive"))
      (node (ref "C39") (pin "1") (pinfunction "1_1") (pintype "passive"))
      (node (ref "C4") (pin "2") (pinfunction "2_2") (pintype "passive"))
      (node (ref "C5") (pin "1") (pinfunction "1_1") (pintype "passive"))
      (node (ref "C56") (pin "2") (pinfunction "2_2") (pintype "passive"))
      (node (ref "C57") (pin "2") (pinfunction "2_2") (pintype "passive"))
      (node (ref "C6") (pin "1") (pinfunction "1_1") (pintype "passive"))
      (node (ref "C62") (pin "2") (pinfunction "2_2") (pintype "passive"))
      (node (ref "C7") (pin "2") (pinfunction "2_2") (pintype "passive"))
      (node (ref "C8") (pin "2") (pinfunction "2_2") (pintype "passive"))
      (node (ref "C80") (pin "2") (pinfunction "2_2") (pintype "passive"))
      (node (ref "C9") (pin "1") (pinfunction "1_1") (pintype "passive"))
      (node (ref "C98") (pin "2") (pinfunction "2_2") (pintype "passive"))
      (node (ref "CP11") (pin "2") (pinfunction "2_2") (pintype "passive"))
      (node (ref "CP12") (pin "2") (pinfunction "2_2") (pintype "passive"))
      (node (ref "CP13") (pin "1") (pinfunction "1_1") (pintype "passive"))
      (node (ref "CP13") (pin "2") (pinfunction "2_2") (pintype "passive"))
      (node (ref "CP13") (pin "3") (pinfunction "3_3") (pintype "passive"))
      (node (ref "CP13") (pin "4") (pinfunction "4_4") (pintype "passive"))
      (node (ref "CP14") (pin "1") (pinfunction "1_1") (pintype "passive"))
      (node (ref "CP14") (pin "2") (pinfunction "2_2") (pintype "passive"))
      (node (ref "CP14") (pin "3") (pinfunction "3_3") (pintype "passive"))
      (node (ref "CP14") (pin "4") (pinfunction "4_4") (pintype "passive"))
      (node (ref "CP16") (pin "2") (pinfunction "2_2") (pintype "passive"))
      (node (ref "CP17") (pin "2") (pinfunction "2_2") (pintype "passive"))
      (node (ref "CP18") (pin "2") (pinfunction "2_2") (pintype "passive"))
      (node (ref "CP2") (pin "2") (pinfunction "2_2") (pintype "passive"))
      (node (ref "CP200") (pin "2") (pinfunction "2_2") (pintype "passive"))
      (node (ref "CP22") (pin "2") (pinfunction "2_2") (pintype "passive"))
      (node (ref "CP23") (pin "2") (pinfunction "2_2") (pintype "passive"))
      (node (ref "CP24") (pin "2") (pinfunction "2_2") (pintype "passive"))
      (node (ref "CP25") (pin "2") (pinfunction "2_2") (pintype "passive"))
      (node (ref "CP3") (pin "2") (pinfunction "2_2") (pintype "passive"))
      (node (ref "CP6") (pin "2") (pinfunction "2_2") (pintype "passive"))
      (node (ref "D201") (pin "1") (pintype "passive"))
      (node (ref "D25") (pin "1") (pinfunction "1_1") (pintype "passive"))
      (node (ref "D32") (pin "1") (pinfunction "1_1") (pintype "passive"))
      (node (ref "D39") (pin "1") (pinfunction "1_1") (pintype "passive"))
      (node (ref "D40") (pin "1") (pinfunction "1_1") (pintype "passive"))
      (node (ref "DZ6") (pin "2") (pintype "passive"))
      (node (ref "J1") (pin "6") (pinfunction "6_6") (pintype "passive"))
      (node (ref "J2") (pin "1") (pinfunction "1_1") (pintype "passive"))
      (node (ref "J2") (pin "10") (pinfunction "10_10") (pintype "passive"))
      (node (ref "J2") (pin "12") (pinfunction "12_12") (pintype "passive"))
      (node (ref "J2") (pin "14") (pinfunction "14_14") (pintype "passive"))
      (node (ref "J2") (pin "16") (pinfunction "16_16") (pintype "passive"))
      (node (ref "J2") (pin "18") (pinfunction "18_18") (pintype "passive"))
      (node (ref "J2") (pin "23") (pinfunction "23_23") (pintype "passive"))
      (node (ref "J2") (pin "24") (pinfunction "24_24") (pintype "passive"))
      (node (ref "JV01") (pin "1") (pinfunction "1_1") (pintype "passive"))
      (node (ref "JV01") (pin "3") (pinfunction "3_3") (pintype "passive"))
      (node (ref "R1") (pin "2") (pinfunction "2_2") (pintype "passive"))
      (node (ref "R10") (pin "1") (pinfunction "1_1") (pintype "passive"))
      (node (ref "R14") (pin "1") (pinfunction "1_1") (pintype "passive"))
      (node (ref "R21") (pin "2") (pinfunction "2_2") (pintype "passive"))
      (node (ref "R211") (pin "2") (pinfunction "2_2") (pintype "passive"))
      (node (ref "R3") (pin "2") (pinfunction "2_2") (pintype "passive"))
      (node (ref "R35") (pin "2") (pinfunction "2_2") (pintype "passive"))
      (node (ref "R37") (pin "2") (pinfunction "2_2") (pintype "passive"))
      (node (ref "R4") (pin "2") (pinfunction "2_2") (pintype "passive"))
      (node (ref "R7") (pin "1") (pinfunction "1_1") (pintype "passive"))
      (node (ref "R9") (pin "2") (pinfunction "2_2") (pintype "passive"))
      (node (ref "RP1") (pin "1") (pinfunction "1_1") (pintype "passive"))
      (node (ref "RP1") (pin "2") (pinfunction "2_2") (pintype "passive"))
      (node (ref "RP1") (pin "3") (pinfunction "3_3") (pintype "passive"))
      (node (ref "RP1") (pin "4") (pinfunction "4_4") (pintype "passive"))
      (node (ref "RP13") (pin "1") (pinfunction "1_1") (pintype "passive"))
      (node (ref "RP13") (pin "2") (pinfunction "2_2") (pintype "passive"))
      (node (ref "RP13") (pin "3") (pinfunction "3_3") (pintype "passive"))
      (node (ref "RP13") (pin "4") (pinfunction "4_4") (pintype "passive"))
      (node (ref "RP14") (pin "1") (pinfunction "1_1") (pintype "passive"))
      (node (ref "RP14") (pin "2") (pinfunction "2_2") (pintype "passive"))
      (node (ref "RP14") (pin "3") (pinfunction "3_3") (pintype "passive"))
      (node (ref "RP14") (pin "4") (pinfunction "4_4") (pintype "passive"))
      (node (ref "RP16") (pin "1") (pinfunction "1_1") (pintype "passive"))
      (node (ref "RP16") (pin "2") (pinfunction "2_2") (pintype "passive"))
      (node (ref "RP16") (pin "3") (pinfunction "3_3") (pintype "passive"))
      (node (ref "RP16") (pin "4") (pinfunction "4_4") (pintype "passive"))
      (node (ref "RP2") (pin "1") (pinfunction "1_1") (pintype "passive"))
      (node (ref "RP2") (pin "2") (pinfunction "2_2") (pintype "passive"))
      (node (ref "RP2") (pin "3") (pinfunction "3_3") (pintype "passive"))
      (node (ref "RP2") (pin "4") (pinfunction "4_4") (pintype "passive"))
      (node (ref "RP27") (pin "1") (pinfunction "1_1") (pintype "passive"))
      (node (ref "RP27") (pin "2") (pinfunction "2_2") (pintype "passive"))
      (node (ref "RP27") (pin "3") (pinfunction "3_3") (pintype "passive"))
      (node (ref "RP27") (pin "4") (pinfunction "4_4") (pintype "passive"))
      (node (ref "RP28") (pin "1") (pinfunction "1_1") (pintype "passive"))
      (node (ref "RP28") (pin "2") (pinfunction "2_2") (pintype "passive"))
      (node (ref "RP28") (pin "3") (pinfunction "3_3") (pintype "passive"))
      (node (ref "RP28") (pin "4") (pinfunction "4_4") (pintype "passive"))
      (node (ref "RP30") (pin "1") (pinfunction "1_1") (pintype "passive"))
      (node (ref "RP30") (pin "2") (pinfunction "2_2") (pintype "passive"))
      (node (ref "RP30") (pin "3") (pinfunction "3_3") (pintype "passive"))
      (node (ref "RP30") (pin "4") (pinfunction "4_4") (pintype "passive"))
      (node (ref "RP4") (pin "1") (pinfunction "1_1") (pintype "passive"))
      (node (ref "RP4") (pin "2") (pinfunction "2_2") (pintype "passive"))
      (node (ref "RP4") (pin "3") (pinfunction "3_3") (pintype "passive"))
      (node (ref "RP4") (pin "4") (pinfunction "4_4") (pintype "passive"))
      (node (ref "RP7") (pin "1") (pinfunction "1_1") (pintype "passive"))
      (node (ref "RP7") (pin "2") (pinfunction "2_2") (pintype "passive"))
      (node (ref "RP7") (pin "3") (pinfunction "3_3") (pintype "passive"))
      (node (ref "RP7") (pin "4") (pinfunction "4_4") (pintype "passive"))
      (node (ref "U1") (pin "2") (pinfunction "Gnd_2") (pintype "passive"))
      (node (ref "U10") (pin "10") (pinfunction "VSSM1_10") (pintype "passive"))
      (node (ref "U10") (pin "132") (pinfunction "VSSX1_132") (pintype "passive"))
      (node (ref "U10") (pin "20") (pinfunction "VSSM2_20") (pintype "passive"))
      (node (ref "U10") (pin "30") (pinfunction "VSSM3_30") (pintype "passive"))
      (node (ref "U10") (pin "49") (pinfunction "VSS2_49") (pintype "passive"))
      (node (ref "U10") (pin "52") (pinfunction "VSSX2_52") (pintype "passive"))
      (node (ref "U10") (pin "57") (pinfunction "VSSPLL_57") (pintype "passive"))
      (node (ref "U10") (pin "60") (pinfunction "TEST_60") (pintype "passive"))
      (node (ref "U10") (pin "76") (pinfunction "VSSA_76") (pintype "passive"))
      (node (ref "U10") (pin "77") (pinfunction "VRL_77") (pintype "passive"))
      (node (ref "U10") (pin "97") (pinfunction "VSS1_97") (pintype "passive"))
      (node (ref "U11") (pin "3") (pinfunction "C_3") (pintype "passive"))
      (node (ref "U13") (pin "2") (pinfunction "GND_2") (pintype "passive"))
      (node (ref "U2") (pin "2") (pinfunction "Gnd_2") (pintype "passive"))
      (node (ref "U21") (pin "5") (pinfunction "GND_5") (pintype "passive"))
      (node (ref "U6") (pin "3") (pinfunction "GND_3") (pintype "passive"))
      (node (ref "U7") (pin "4") (pinfunction "Vss_4") (pintype "passive"))
      (node (ref "U8") (pin "1") (pinfunction "A0_1") (pintype "passive"))
      (node (ref "U8") (pin "2") (pinfunction "A1_2") (pintype "passive"))
      (node (ref "U8") (pin "3") (pinfunction "A2_3") (pintype "passive"))
      (node (ref "U8") (pin "4") (pinfunction "GND_4") (pintype "passive"))
      (node (ref "U8") (pin "7") (pinfunction "WP_7") (pintype "passive"))
      (node (ref "UART") (pin "1") (pinfunction "1_1") (pintype "passive"))
    )
    (net (code "90") (name "Net-(BT1-+)") (class "Default")
      (node (ref "BT1") (pin "1") (pinfunction "+_1") (pintype "passive"))
      (node (ref "U7") (pin "3") (pinfunction "VBAT_3") (pintype "passive"))
    )
    (net (code "91") (name "Net-(C7-Pad1)") (class "Default")
      (node (ref "C7") (pin "1") (pinfunction "1_1") (pintype "passive"))
      (node (ref "R12") (pin "1") (pinfunction "1_1") (pintype "passive"))
    )
    (net (code "92") (name "Net-(C8-Pad1)") (class "Default")
      (node (ref "C8") (pin "1") (pinfunction "1_1") (pintype "passive"))
      (node (ref "R13") (pin "1") (pinfunction "1_1") (pintype "passive"))
    )
    (net (code "93") (name "Net-(C52-Pad2)") (class "Default")
      (node (ref "C52") (pin "2") (pinfunction "2_2") (pintype "passive"))
      (node (ref "C98") (pin "1") (pinfunction "1_1") (pintype "passive"))
      (node (ref "R54") (pin "2") (pinfunction "2_2") (pintype "passive"))
    )
    (net (code "94") (name "Net-(C201-Pad1)") (class "Default")
      (node (ref "C201") (pin "1") (pinfunction "1_1") (pintype "passive"))
      (node (ref "R210") (pin "2") (pinfunction "2_2") (pintype "passive"))
      (node (ref "R211") (pin "1") (pinfunction "1_1") (pintype "passive"))
    )
    (net (code "95") (name "Net-(C205-Pad1)") (class "Default")
      (node (ref "C205") (pin "1") (pinfunction "1_1") (pintype "passive"))
      (node (ref "R233") (pin "1") (pinfunction "1_1") (pintype "passive"))
    )
    (net (code "96") (name "Net-(D201-Pad3)") (class "Default")
      (node (ref "D201") (pin "3") (pintype "passive"))
      (node (ref "JV01") (pin "2") (pinfunction "2_2") (pintype "passive"))
      (node (ref "R210") (pin "1") (pinfunction "1_1") (pintype "passive"))
    )
    (net (code "97") (name "Net-(J2-Pad2)") (class "Default")
      (node (ref "J2") (pin "2") (pinfunction "2_2") (pintype "passive"))
      (node (ref "R138") (pin "1") (pinfunction "1_1") (pintype "passive"))
    )
    (net (code "98") (name "Net-(J2-Pad3)") (class "Default")
      (node (ref "J2") (pin "3") (pinfunction "3_3") (pintype "passive"))
      (node (ref "R148") (pin "1") (pinfunction "1_1") (pintype "passive"))
    )
    (net (code "99") (name "Net-(J2-Pad4)") (class "Default")
      (node (ref "J2") (pin "4") (pinfunction "4_4") (pintype "passive"))
      (node (ref "R149") (pin "1") (pinfunction "1_1") (pintype "passive"))
    )
    (net (code "100") (name "Net-(J2-Pad5)") (class "Default")
      (node (ref "J2") (pin "5") (pinfunction "5_5") (pintype "passive"))
      (node (ref "R152") (pin "1") (pinfunction "1_1") (pintype "passive"))
    )
    (net (code "101") (name "Net-(J2-Pad6)") (class "Default")
      (node (ref "J2") (pin "6") (pinfunction "6_6") (pintype "passive"))
      (node (ref "R153") (pin "1") (pinfunction "1_1") (pintype "passive"))
    )
    (net (code "102") (name "Net-(J2-Pad7)") (class "Default")
      (node (ref "J2") (pin "7") (pinfunction "7_7") (pintype "passive"))
      (node (ref "R154") (pin "1") (pinfunction "1_1") (pintype "passive"))
    )
    (net (code "103") (name "Net-(J2-Pad8)") (class "Default")
      (node (ref "J2") (pin "8") (pinfunction "8_8") (pintype "passive"))
      (node (ref "R155") (pin "1") (pinfunction "1_1") (pintype "passive"))
    )
    (net (code "104") (name "Net-(J2-Pad9)") (class "Default")
      (node (ref "J2") (pin "9") (pinfunction "9_9") (pintype "passive"))
      (node (ref "R156") (pin "1") (pinfunction "1_1") (pintype "passive"))
    )
    (net (code "105") (name "Net-(L5-Pad1)") (class "Default")
      (node (ref "L5") (pin "1") (pinfunction "1_1") (pintype "passive"))
      (node (ref "UART") (pin "4") (pinfunction "4_4") (pintype "passive"))
    )
    (net (code "106") (name "Net-(U2-Vref)") (class "Default")
      (node (ref "C4") (pin "1") (pinfunction "1_1") (pintype "passive"))
      (node (ref "U2") (pin "5") (pinfunction "Vref_5") (pintype "passive"))
    )
    (net (code "107") (name "Net-(U6-PFI)") (class "Default")
      (node (ref "R35") (pin "1") (pinfunction "1_1") (pintype "passive"))
      (node (ref "U6") (pin "4") (pinfunction "PFI_4") (pintype "passive"))
    )
    (net (code "108") (name "Net-(U6-~{MR})") (class "Default")
      (node (ref "R33") (pin "1") (pinfunction "1_1") (pintype "passive"))
      (node (ref "U6") (pin "1") (pinfunction "~{MR}_1") (pintype "passive"))
      (node (ref "U6") (pin "8") (pinfunction "~{WDO}_8") (pintype "passive"))
    )
    (net (code "109") (name "Net-(U6-~{REST})") (class "Default")
      (node (ref "R34") (pin "1") (pinfunction "1_1") (pintype "passive"))
      (node (ref "U6") (pin "7") (pinfunction "~{REST}_7") (pintype "passive"))
    )
    (net (code "110") (name "Net-(U7-TRQ)") (class "Default")
      (node (ref "RP3") (pin "2") (pinfunction "2_2") (pintype "passive"))
      (node (ref "U7") (pin "7") (pinfunction "TRQ_7") (pintype "passive"))
    )
    (net (code "111") (name "Net-(U7-XI)") (class "Default")
      (node (ref "U7") (pin "1") (pinfunction "XI_1") (pintype "passive"))
      (node (ref "YC2") (pin "2") (pinfunction "2_2") (pintype "passive"))
    )
    (net (code "112") (name "Net-(U7-XO)") (class "Default")
      (node (ref "U7") (pin "2") (pinfunction "XO_2") (pintype "passive"))
      (node (ref "YC2") (pin "1") (pinfunction "1_1") (pintype "passive"))
    )
    (net (code "113") (name "Net-(U10-ACC0{slash}PK4)") (class "Default")
      (node (ref "RP16") (pin "5") (pinfunction "5_5") (pintype "passive"))
      (node (ref "U10") (pin "43") (pinfunction "ACC0/PK4_43") (pintype "passive"))
    )
    (net (code "114") (name "Net-(U10-ACC1{slash}PK5)") (class "Default")
      (node (ref "R10") (pin "2") (pinfunction "2_2") (pintype "passive"))
      (node (ref "U10") (pin "44") (pinfunction "ACC1/PK5_44") (pintype "passive"))
    )
    (net (code "115") (name "Net-(U10-ACC2{slash}PK6)") (class "Default")
      (node (ref "R21") (pin "1") (pinfunction "1_1") (pintype "passive"))
      (node (ref "U10") (pin "61") (pinfunction "ACC2/PK6_61") (pintype "passive"))
    )
    (net (code "116") (name "Net-(U10-AN14{slash}PL6)") (class "Default")
      (node (ref "RP4") (pin "8") (pinfunction "8_8") (pintype "passive"))
      (node (ref "U10") (pin "3") (pinfunction "AN14/PL6_3") (pintype "passive"))
    )
    (net (code "117") (name "Net-(U10-AN15{slash}PL7)") (class "Default")
      (node (ref "RP4") (pin "7") (pinfunction "7_7") (pintype "passive"))
      (node (ref "U10") (pin "4") (pinfunction "AN15/PL7_4") (pintype "passive"))
    )
    (net (code "118") (name "Net-(U10-EXTAL)") (class "Default")
      (node (ref "R53") (pin "2") (pinfunction "2_2") (pintype "passive"))
      (node (ref "U10") (pin "58") (pinfunction "EXTAL_58") (pintype "passive"))
    )
    (net (code "119") (name "Net-(U10-KWAD0{slash}AD0)") (class "Default")
      (node (ref "U10") (pin "80") (pinfunction "KWAD0/AD0_80") (pintype "passive"))
      (node (ref "U11") (pin "2") (pinfunction "B_2") (pintype "input"))
    )
    (net (code "120") (name "Net-(U10-KWAD1{slash}AD1)") (class "Default")
      (node (ref "R7") (pin "2") (pinfunction "2_2") (pintype "passive"))
      (node (ref "U10") (pin "81") (pinfunction "KWAD1/AD1_81") (pintype "passive"))
    )
    (net (code "121") (name "Net-(U10-M0C0M)") (class "Default")
      (node (ref "CP14") (pin "5") (pinfunction "5_5") (pintype "passive"))
      (node (ref "RP12") (pin "4") (pinfunction "4_4") (pintype "input"))
      (node (ref "U10") (pin "11") (pinfunction "M0C0M_11") (pintype "passive"))
    )
    (net (code "122") (name "Net-(U10-M0C0P)") (class "Default")
      (node (ref "CP14") (pin "6") (pinfunction "6_6") (pintype "passive"))
      (node (ref "RP12") (pin "3") (pinfunction "3_3") (pintype "input"))
      (node (ref "U10") (pin "12") (pinfunction "M0C0P_12") (pintype "passive"))
    )
    (net (code "123") (name "Net-(U10-M0C1M)") (class "Default")
      (node (ref "CP14") (pin "7") (pinfunction "7_7") (pintype "passive"))
      (node (ref "RP12") (pin "2") (pinfunction "2_2") (pintype "input"))
      (node (ref "U10") (pin "13") (pinfunction "M0C1M_13") (pintype "passive"))
    )
    (net (code "124") (name "Net-(U10-M0C1P)") (class "Default")
      (node (ref "CP14") (pin "8") (pinfunction "8_8") (pintype "passive"))
      (node (ref "RP12") (pin "1") (pinfunction "1_1") (pintype "input"))
      (node (ref "U10") (pin "14") (pinfunction "M0C1P_14") (pintype "passive"))
    )
    (net (code "125") (name "Net-(U10-M1C0M)") (class "Default")
      (node (ref "RP13") (pin "8") (pinfunction "8_8") (pintype "passive"))
      (node (ref "U10") (pin "15") (pinfunction "M1C0M_15") (pintype "passive"))
    )
    (net (code "126") (name "Net-(U10-M1C0P)") (class "Default")
      (node (ref "RP13") (pin "7") (pinfunction "7_7") (pintype "passive"))
      (node (ref "U10") (pin "16") (pinfunction "M1C0P_16") (pintype "passive"))
    )
    (net (code "127") (name "Net-(U10-M1C1M)") (class "Default")
      (node (ref "RP13") (pin "6") (pinfunction "6_6") (pintype "passive"))
      (node (ref "U10") (pin "17") (pinfunction "M1C1M_17") (pintype "passive"))
    )
    (net (code "128") (name "Net-(U10-M1C1P)") (class "Default")
      (node (ref "RP13") (pin "5") (pinfunction "5_5") (pintype "passive"))
      (node (ref "U10") (pin "18") (pinfunction "M1C1P_18") (pintype "passive"))
    )
    (net (code "129") (name "Net-(U10-M3C0M)") (class "Default")
      (node (ref "RP7") (pin "8") (pinfunction "8_8") (pintype "passive"))
      (node (ref "U10") (pin "25") (pinfunction "M3C0M_25") (pintype "passive"))
    )
    (net (code "130") (name "Net-(U10-M3C0P)") (class "Default")
      (node (ref "RP7") (pin "7") (pinfunction "7_7") (pintype "passive"))
      (node (ref "U10") (pin "26") (pinfunction "M3C0P_26") (pintype "passive"))
    )
    (net (code "131") (name "Net-(U10-M3C1M)") (class "Default")
      (node (ref "RP7") (pin "6") (pinfunction "6_6") (pintype "passive"))
      (node (ref "U10") (pin "27") (pinfunction "M3C1M_27") (pintype "passive"))
    )
    (net (code "132") (name "Net-(U10-M3C1P)") (class "Default")
      (node (ref "RP7") (pin "5") (pinfunction "5_5") (pintype "passive"))
      (node (ref "U10") (pin "28") (pinfunction "M3C1P_28") (pintype "passive"))
    )
    (net (code "133") (name "Net-(U10-M4C0M)") (class "Default")
      (node (ref "RP4") (pin "6") (pinfunction "6_6") (pintype "passive"))
      (node (ref "U10") (pin "5") (pinfunction "M4C0M_5") (pintype "passive"))
    )
    (net (code "134") (name "Net-(U10-M5C0M)") (class "Default")
      (node (ref "CP13") (pin "5") (pinfunction "5_5") (pintype "passive"))
      (node (ref "RP11") (pin "4") (pinfunction "4_4") (pintype "input"))
      (node (ref "U10") (pin "31") (pinfunction "M5C0M_31") (pintype "passive"))
    )
    (net (code "135") (name "Net-(U10-M5C0P)") (class "Default")
      (node (ref "CP13") (pin "6") (pinfunction "6_6") (pintype "passive"))
      (node (ref "RP11") (pin "3") (pinfunction "3_3") (pintype "input"))
      (node (ref "U10") (pin "32") (pinfunction "M5C0P_32") (pintype "passive"))
    )
    (net (code "136") (name "Net-(U10-M5C1M)") (class "Default")
      (node (ref "CP13") (pin "7") (pinfunction "7_7") (pintype "passive"))
      (node (ref "RP11") (pin "2") (pinfunction "2_2") (pintype "input"))
      (node (ref "U10") (pin "33") (pinfunction "M5C1M_33") (pintype "passive"))
    )
    (net (code "137") (name "Net-(U10-M5C1P)") (class "Default")
      (node (ref "CP13") (pin "8") (pinfunction "8_8") (pintype "passive"))
      (node (ref "RP11") (pin "1") (pinfunction "1_1") (pintype "input"))
      (node (ref "U10") (pin "34") (pinfunction "M5C1P_34") (pintype "passive"))
    )
    (net (code "138") (name "Net-(U10-PA3{slash}FP11)") (class "Default")
      (node (ref "RP28") (pin "8") (pinfunction "8_8") (pintype "passive"))
      (node (ref "U10") (pin "114") (pinfunction "PA3/FP11_114") (pintype "passive"))
    )
    (net (code "139") (name "Net-(U10-PA4{slash}FP12)") (class "Default")
      (node (ref "RP28") (pin "7") (pinfunction "7_7") (pintype "passive"))
      (node (ref "U10") (pin "115") (pinfunction "PA4/FP12_115") (pintype "passive"))
    )
    (net (code "140") (name "Net-(U10-PA5{slash}FP13)") (class "Default")
      (node (ref "RP28") (pin "6") (pinfunction "6_6") (pintype "passive"))
      (node (ref "U10") (pin "116") (pinfunction "PA5/FP13_116") (pintype "passive"))
    )
    (net (code "141") (name "Net-(U10-PA6{slash}FP14)") (class "Default")
      (node (ref "RP28") (pin "5") (pinfunction "5_5") (pintype "passive"))
      (node (ref "U10") (pin "117") (pinfunction "PA6/FP14_117") (pintype "passive"))
    )
    (net (code "142") (name "Net-(U10-PA7{slash}FP15)") (class "Default")
      (node (ref "RP30") (pin "8") (pinfunction "8_8") (pintype "passive"))
      (node (ref "U10") (pin "118") (pinfunction "PA7/FP15_118") (pintype "passive"))
    )
    (net (code "143") (name "Net-(U10-PC0{slash}DAT8)") (class "Default")
      (node (ref "RP27") (pin "7") (pinfunction "7_7") (pintype "passive"))
      (node (ref "U10") (pin "123") (pinfunction "PC0/DAT8_123") (pintype "passive"))
    )
    (net (code "144") (name "Net-(U10-PC1{slash}DAT9)") (class "Default")
      (node (ref "RP27") (pin "6") (pinfunction "6_6") (pintype "passive"))
      (node (ref "U10") (pin "124") (pinfunction "PC1/DAT9_124") (pintype "passive"))
    )
    (net (code "145") (name "Net-(U10-PC2{slash}DAT10)") (class "Default")
      (node (ref "RP27") (pin "5") (pinfunction "5_5") (pintype "passive"))
      (node (ref "U10") (pin "125") (pinfunction "PC2/DAT10_125") (pintype "passive"))
    )
    (net (code "146") (name "Net-(U10-PC3{slash}DAT11)") (class "Default")
      (node (ref "RP14") (pin "8") (pinfunction "8_8") (pintype "passive"))
      (node (ref "U10") (pin "126") (pinfunction "PC3/DAT11_126") (pintype "passive"))
    )
    (net (code "147") (name "Net-(U10-PC4{slash}DAT12)") (class "Default")
      (node (ref "RP2") (pin "6") (pinfunction "6_6") (pintype "passive"))
      (node (ref "U10") (pin "133") (pinfunction "PC4/DAT12_133") (pintype "passive"))
    )
    (net (code "148") (name "Net-(U10-PC5{slash}DAT13)") (class "Default")
      (node (ref "RP2") (pin "5") (pinfunction "5_5") (pintype "passive"))
      (node (ref "U10") (pin "134") (pinfunction "PC5/DAT13_134") (pintype "passive"))
    )
    (net (code "149") (name "Net-(U10-PC6{slash}DAT14)") (class "Default")
      (node (ref "RP1") (pin "8") (pinfunction "8_8") (pintype "passive"))
      (node (ref "U10") (pin "135") (pinfunction "PC6/DAT14_135") (pintype "passive"))
    )
    (net (code "150") (name "Net-(U10-PC7{slash}DAT15)") (class "Default")
      (node (ref "RP1") (pin "7") (pinfunction "7_7") (pintype "passive"))
      (node (ref "U10") (pin "136") (pinfunction "PC7/DAT15_136") (pintype "passive"))
    )
    (net (code "151") (name "Net-(U10-PE0{slash}~{XIRQ})") (class "Default")
      (node (ref "R9") (pin "1") (pinfunction "1_1") (pintype "passive"))
      (node (ref "U10") (pin "75") (pinfunction "PE0/~{XIRQ}_75") (pintype "passive"))
    )
    (net (code "152") (name "Net-(U10-PE2{slash}R{slash}~{W})") (class "Default")
      (node (ref "RP14") (pin "7") (pinfunction "7_7") (pintype "passive"))
      (node (ref "U10") (pin "127") (pinfunction "PE2/R/~{W}_127") (pintype "passive"))
    )
    (net (code "153") (name "Net-(U10-PE3{slash}~{LSTRB}{slash}LDS)") (class "Default")
      (node (ref "RP14") (pin "6") (pinfunction "6_6") (pintype "passive"))
      (node (ref "U10") (pin "128") (pinfunction "PE3/~{LSTRB}/LDS_128") (pintype "passive"))
    )
    (net (code "154") (name "Net-(U10-PE7{slash}ECLKX2{slash}XCLKS)") (class "Default")
      (node (ref "RP14") (pin "5") (pinfunction "5_5") (pintype "passive"))
      (node (ref "U10") (pin "129") (pinfunction "PE7/ECLKX2/XCLKS_129") (pintype "passive"))
    )
    (net (code "155") (name "Net-(U10-PK7{slash}~{EWAIT}{slash}ROMCTL)") (class "Default")
      (node (ref "RP2") (pin "7") (pinfunction "7_7") (pintype "passive"))
      (node (ref "U10") (pin "130") (pinfunction "PK7/~{EWAIT}/ROMCTL_130") (pintype "passive"))
    )
    (net (code "156") (name "Net-(U10-PL0{slash}FP16)") (class "Default")
      (node (ref "RP30") (pin "7") (pinfunction "7_7") (pintype "passive"))
      (node (ref "U10") (pin "119") (pinfunction "PL0/FP16_119") (pintype "passive"))
    )
    (net (code "157") (name "Net-(U10-PL1{slash}FP17)") (class "Default")
      (node (ref "RP30") (pin "6") (pinfunction "6_6") (pintype "passive"))
      (node (ref "U10") (pin "120") (pinfunction "PL1/FP17_120") (pintype "passive"))
    )
    (net (code "158") (name "Net-(U10-PL2{slash}FP18)") (class "Default")
      (node (ref "RP30") (pin "5") (pinfunction "5_5") (pintype "passive"))
      (node (ref "U10") (pin "121") (pinfunction "PL2/FP18_121") (pintype "passive"))
    )
    (net (code "159") (name "Net-(U10-PL3{slash}FP19)") (class "Default")
      (node (ref "RP27") (pin "8") (pinfunction "8_8") (pintype "passive"))
      (node (ref "U10") (pin "122") (pinfunction "PL3/FP19_122") (pintype "passive"))
    )
    (net (code "160") (name "Net-(U10-PT0{slash}IOC0)") (class "Default")
      (node (ref "RP1") (pin "6") (pinfunction "6_6") (pintype "passive"))
      (node (ref "U10") (pin "137") (pinfunction "PT0/IOC0_137") (pintype "passive"))
    )
    (net (code "161") (name "Net-(U10-PT1{slash}IOC1)") (class "Default")
      (node (ref "RP1") (pin "5") (pinfunction "5_5") (pintype "passive"))
      (node (ref "U10") (pin "138") (pinfunction "PT1/IOC1_138") (pintype "passive"))
    )
    (net (code "162") (name "Net-(U10-PWM1{slash}PP1)") (class "Default")
      (node (ref "RP16") (pin "8") (pinfunction "8_8") (pintype "passive"))
      (node (ref "U10") (pin "40") (pinfunction "PWM1/PP1_40") (pintype "passive"))
    )
    (net (code "163") (name "Net-(U10-RXD1{slash}PS2)") (class "Default")
      (node (ref "R14") (pin "2") (pinfunction "2_2") (pintype "passive"))
      (node (ref "U10") (pin "47") (pinfunction "RXD1/PS2_47") (pintype "passive"))
    )
    (net (code "164") (name "Net-(U10-SCL1{slash}PWM7)") (class "Default")
      (node (ref "RP16") (pin "6") (pinfunction "6_6") (pintype "passive"))
      (node (ref "U10") (pin "42") (pinfunction "SCL1/PWM7_42") (pintype "passive"))
    )
    (net (code "165") (name "Net-(U10-SDA1{slash}PWM6)") (class "Default")
      (node (ref "RP16") (pin "7") (pinfunction "7_7") (pintype "passive"))
      (node (ref "U10") (pin "41") (pinfunction "SDA1/PWM6_41") (pintype "passive"))
    )
    (net (code "166") (name "Net-(U10-VDD1)") (class "Default")
      (node (ref "C34") (pin "1") (pinfunction "1_1") (pintype "passive"))
      (node (ref "U10") (pin "96") (pinfunction "VDD1_96") (pintype "passive"))
    )
    (net (code "167") (name "Net-(U10-VDDPLL)") (class "Default")
      (node (ref "C48") (pin "2") (pinfunction "2_2") (pintype "passive"))
      (node (ref "C52") (pin "1") (pinfunction "1_1") (pintype "passive"))
      (node (ref "U10") (pin "55") (pinfunction "VDDPLL_55") (pintype "passive"))
    )
    (net (code "168") (name "Net-(U10-XFC)") (class "Default")
      (node (ref "C48") (pin "1") (pinfunction "1_1") (pintype "passive"))
      (node (ref "R54") (pin "1") (pinfunction "1_1") (pintype "passive"))
      (node (ref "U10") (pin "56") (pinfunction "XFC_56") (pintype "passive"))
    )
    (net (code "169") (name "Net-(U10-~{IRQ}{slash}PE1)") (class "Default")
      (node (ref "R142") (pin "1") (pinfunction "1_1") (pintype "passive"))
      (node (ref "U10") (pin "72") (pinfunction "~{IRQ}/PE1_72") (pintype "passive"))
    )
    (net (code "170") (name "Net-(U13-OUT)") (class "Default")
      (node (ref "R53") (pin "1") (pinfunction "1_1") (pintype "passive"))
      (node (ref "U13") (pin "3") (pinfunction "OUT_3") (pintype "passive"))
    )
    (net (code "171") (name "Net-(U21-OUT1)") (class "Default")
      (node (ref "R233") (pin "2") (pinfunction "2_2") (pintype "passive"))
      (node (ref "U21") (pin "8") (pinfunction "OUT1_8") (pintype "passive"))
    )
    (net (code "172") (name "Net-(U21-VCC)") (class "Default")
      (node (ref "C208") (pin "1") (pinfunction "1_1") (pintype "passive"))
      (node (ref "CP200") (pin "1") (pinfunction "1_1") (pintype "passive"))
      (node (ref "L205") (pin "2") (pinfunction "2_2") (pintype "passive"))
      (node (ref "U21") (pin "4") (pinfunction "VCC_4") (pintype "passive"))
    )
    (net (code "173") (name "unconnected-(DZ6-Pad5)") (class "Default")
      (node (ref "DZ6") (pin "5") (pintype "passive"))
    )
    (net (code "174") (name "unconnected-(J1-Pad2)") (class "Default")
      (node (ref "J1") (pin "2") (pinfunction "2_2") (pintype "passive"))
    )
    (net (code "175") (name "unconnected-(J1-Pad3)") (class "Default")
      (node (ref "J1") (pin "3") (pinfunction "3_3") (pintype "passive"))
    )
    (net (code "176") (name "unconnected-(J2-Pad13)") (class "Default")
      (node (ref "J2") (pin "13") (pinfunction "13_13") (pintype "passive"))
    )
    (net (code "177") (name "unconnected-(J2-Pad15)") (class "Default")
      (node (ref "J2") (pin "15") (pinfunction "15_15") (pintype "passive"))
    )
    (net (code "178") (name "unconnected-(J2-Pad17)") (class "Default")
      (node (ref "J2") (pin "17") (pinfunction "17_17") (pintype "passive"))
    )
    (net (code "179") (name "unconnected-(RP2-Pad8)") (class "Default")
      (node (ref "RP2") (pin "8") (pinfunction "8_8") (pintype "passive"))
    )
    (net (code "180") (name "unconnected-(RP3-Pad1)") (class "Default")
      (node (ref "RP3") (pin "1") (pinfunction "1_1") (pintype "passive"))
    )
    (net (code "181") (name "unconnected-(RP4-Pad5)") (class "Default")
      (node (ref "RP4") (pin "5") (pinfunction "5_5") (pintype "passive"))
    )
    (net (code "182") (name "unconnected-(U6-~{PFO}-Pad5)") (class "Default")
      (node (ref "U6") (pin "5") (pinfunction "~{PFO}_5") (pintype "passive+no_connect"))
    )
    (net (code "183") (name "unconnected-(U10-XTAL-Pad59)") (class "Default")
      (node (ref "U10") (pin "59") (pinfunction "XTAL_59") (pintype "passive+no_connect"))
    )
    (net (code "184") (name "unconnected-(U13-OE-Pad1)") (class "Default")
      (node (ref "U13") (pin "1") (pinfunction "OE_1") (pintype "passive+no_connect"))
    )
    (net (code "185") (name "unconnected-(U21-IN2-Pad2)") (class "Default")
      (node (ref "U21") (pin "2") (pinfunction "IN2_2") (pintype "passive"))
    )
    (net (code "186") (name "unconnected-(U21-IN3-Pad3)") (class "Default")
      (node (ref "U21") (pin "3") (pinfunction "IN3_3") (pintype "passive"))
    )
    (net (code "187") (name "unconnected-(U21-OUT2-Pad7)") (class "Default")
      (node (ref "U21") (pin "7") (pinfunction "OUT2_7") (pintype "passive"))
    )
    (net (code "188") (name "unconnected-(U21-OUT3-Pad6)") (class "Default")
      (node (ref "U21") (pin "6") (pinfunction "OUT3_6") (pintype "passive"))
    )
  )
)
